# SCH_ESP8266.net
KiCad netlist of a schematic drawn in Altium Designer
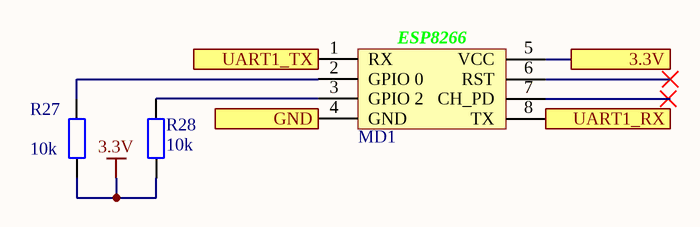
[diagram p0: SCH_ESP8266.SchDoc]

(export (version "E")
  (design (tool "Eeschema 10.0.6"))
  (components
    (comp (ref "MD1")
      (value "ESP8266 Module")
      (footprint "ESP2866 Module")
      (libsource (lib "Altium_Lib_by_KhueNguyenCreator") (part "ESP8266 Module"))
    )
    (comp (ref "R27")
      (value "10k")
      (footprint "tro smd 0805")
      (description "Dán")
      (libsource (lib "Altium_Lib_by_KhueNguyenCreator") (part "Tro 0805 5% 10k"))
    )
    (comp (ref "R28")
      (value "10k")
      (footprint "tro smd 0805")
      (description "Dán")
      (libsource (lib "Altium_Lib_by_KhueNguyenCreator") (part "Tro 0805 5% 10k"))
    )
  )
  (nets
    (net (code "1") (name "/GND") (class "Default")
      (node (ref "MD1") (pin "4") (pinfunction "GND_4") (pintype "passive"))
    )
    (net (code "2") (name "/UART1_RX") (class "Default")
      (node (ref "MD1") (pin "8") (pinfunction "TX_8") (pintype "passive"))
    )
    (net (code "3") (name "/UART1_TX") (class "Default")
      (node (ref "MD1") (pin "1") (pinfunction "RX_1") (pintype "passive"))
    )
    (net (code "4") (name "3.3V") (class "Default")
      (node (ref "MD1") (pin "5") (pinfunction "VCC_5") (pintype "passive"))
      (node (ref "R27") (pin "1") (pinfunction "1_1") (pintype "passive"))
      (node (ref "R28") (pin "1") (pinfunction "1_1") (pintype "passive"))
    )
    (net (code "5") (name "Net-(MD1-GPIO_0)") (class "Default")
      (node (ref "MD1") (pin "2") (pinfunction "GPIO_0_2") (pintype "passive"))
      (node (ref "R27") (pin "2") (pinfunction "2_2") (pintype "passive"))
    )
    (net (code "6") (name "Net-(MD1-GPIO_2)") (class "Default")
      (node (ref "MD1") (pin "3") (pinfunction "GPIO_2_3") (pintype "passive"))
      (node (ref "R28") (pin "2") (pinfunction "2_2") (pintype "passive"))
    )
    (net (code "7") (name "unconnected-(MD1-CH_PD-Pad7)") (class "Default")
      (node (ref "MD1") (pin "7") (pinfunction "CH_PD_7") (pintype "passive"))
    )
    (net (code "8") (name "unconnected-(MD1-RST-Pad6)") (class "Default")
      (node (ref "MD1") (pin "6") (pinfunction "RST_6") (pintype "passive+no_connect"))
    )
  )
)
